# 10leds.net
KiCad netlist of a schematic drawn in EAGLE
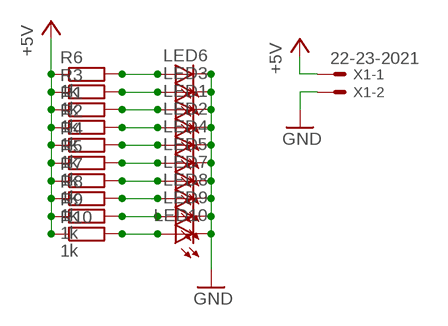
[diagram p0: schematic, sheet 1]

(export (version "E")
  (design (tool "Eeschema 10.0.6"))
  (components
    (comp (ref "LED1")
      (value "LED3MM")
      (footprint "eagle-import:LED3MM")
      (libsource (lib "eagle-import") (part "LED3MM"))
    )
    (comp (ref "LED2")
      (value "LED3MM")
      (footprint "eagle-import:LED3MM")
      (libsource (lib "eagle-import") (part "LED3MM"))
    )
    (comp (ref "LED3")
      (value "LED3MM")
      (footprint "eagle-import:LED3MM")
      (libsource (lib "eagle-import") (part "LED3MM"))
    )
    (comp (ref "LED4")
      (value "LED3MM")
      (footprint "eagle-import:LED3MM")
      (libsource (lib "eagle-import") (part "LED3MM"))
    )
    (comp (ref "LED5")
      (value "LED3MM")
      (footprint "eagle-import:LED3MM")
      (libsource (lib "eagle-import") (part "LED3MM"))
    )
    (comp (ref "LED6")
      (value "LED3MM")
      (footprint "eagle-import:LED3MM")
      (libsource (lib "eagle-import") (part "LED3MM"))
    )
    (comp (ref "LED7")
      (value "LED3MM")
      (footprint "eagle-import:LED3MM")
      (libsource (lib "eagle-import") (part "LED3MM"))
    )
    (comp (ref "LED8")
      (value "LED3MM")
      (footprint "eagle-import:LED3MM")
      (libsource (lib "eagle-import") (part "LED3MM"))
    )
    (comp (ref "LED9")
      (value "LED3MM")
      (footprint "eagle-import:LED3MM")
      (libsource (lib "eagle-import") (part "LED3MM"))
    )
    (comp (ref "LED10")
      (value "LED3MM")
      (footprint "eagle-import:LED3MM")
      (libsource (lib "eagle-import") (part "LED3MM"))
    )
    (comp (ref "R1")
      (value "1k")
      (footprint "eagle-import:M1206")
      (libsource (lib "eagle-import") (part "R-EU_M1206"))
    )
    (comp (ref "R2")
      (value "1k")
      (footprint "eagle-import:M1206")
      (libsource (lib "eagle-import") (part "R-EU_M1206"))
    )
    (comp (ref "R3")
      (value "1k")
      (footprint "eagle-import:M1206")
      (libsource (lib "eagle-import") (part "R-EU_M1206"))
    )
    (comp (ref "R4")
      (value "1k")
      (footprint "eagle-import:M1206")
      (libsource (lib "eagle-import") (part "R-EU_M1206"))
    )
    (comp (ref "R5")
      (value "1k")
      (footprint "eagle-import:M1206")
      (libsource (lib "eagle-import") (part "R-EU_M1206"))
    )
    (comp (ref "R6")
      (value "1k")
      (footprint "eagle-import:M1206")
      (libsource (lib "eagle-import") (part "R-EU_M1206"))
    )
    (comp (ref "R7")
      (value "1k")
      (footprint "eagle-import:M1206")
      (libsource (lib "eagle-import") (part "R-EU_M1206"))
    )
    (comp (ref "R8")
      (value "1k")
      (footprint "eagle-import:M1206")
      (libsource (lib "eagle-import") (part "R-EU_M1206"))
    )
    (comp (ref "R9")
      (value "1k")
      (footprint "eagle-import:M1206")
      (libsource (lib "eagle-import") (part "R-EU_M1206"))
    )
    (comp (ref "R10")
      (value "1k")
      (footprint "eagle-import:M1206")
      (libsource (lib "eagle-import") (part "R-EU_M1206"))
    )
    (comp (ref "X1")
      (value "22-23-2021")
      (footprint "eagle-import:22-23-2021")
      (fields (field (name "MF") "MOLEX"))
      (libsource (lib "eagle-import") (part "22-23-2021"))
    )
  )
  (nets
    (net (code "1") (name "+5V") (class "Default")
      (node (ref "R1") (pin "1") (pinfunction "1_1") (pintype "passive"))
      (node (ref "R10") (pin "1") (pinfunction "1_1") (pintype "passive"))
      (node (ref "R2") (pin "1") (pinfunction "1_1") (pintype "passive"))
      (node (ref "R3") (pin "1") (pinfunction "1_1") (pintype "passive"))
      (node (ref "R4") (pin "1") (pinfunction "1_1") (pintype "passive"))
      (node (ref "R5") (pin "1") (pinfunction "1_1") (pintype "passive"))
      (node (ref "R6") (pin "1") (pinfunction "1_1") (pintype "passive"))
      (node (ref "R7") (pin "1") (pinfunction "1_1") (pintype "passive"))
      (node (ref "R8") (pin "1") (pinfunction "1_1") (pintype "passive"))
      (node (ref "R9") (pin "1") (pinfunction "1_1") (pintype "passive"))
      (node (ref "X1") (pin "1") (pinfunction "S_1") (pintype "passive"))
    )
    (net (code "2") (name "GND") (class "Default")
      (node (ref "LED1") (pin "K") (pinfunction "C_K") (pintype "passive"))
      (node (ref "LED10") (pin "K") (pinfunction "C_K") (pintype "passive"))
      (node (ref "LED2") (pin "K") (pinfunction "C_K") (pintype "passive"))
      (node (ref "LED3") (pin "K") (pinfunction "C_K") (pintype "passive"))
      (node (ref "LED4") (pin "K") (pinfunction "C_K") (pintype "passive"))
      (node (ref "LED5") (pin "K") (pinfunction "C_K") (pintype "passive"))
      (node (ref "LED6") (pin "K") (pinfunction "C_K") (pintype "passive"))
      (node (ref "LED7") (pin "K") (pinfunction "C_K") (pintype "passive"))
      (node (ref "LED8") (pin "K") (pinfunction "C_K") (pintype "passive"))
      (node (ref "LED9") (pin "K") (pinfunction "C_K") (pintype "passive"))
      (node (ref "X1") (pin "2") (pinfunction "S_2") (pintype "passive"))
    )
    (net (code "3") (name "Net-(LED1-PadA)") (class "Default")
      (node (ref "LED1") (pin "A") (pinfunction "A_A") (pintype "passive"))
      (node (ref "R1") (pin "2") (pinfunction "2_2") (pintype "passive"))
    )
    (net (code "4") (name "Net-(LED2-PadA)") (class "Default")
      (node (ref "LED2") (pin "A") (pinfunction "A_A") (pintype "passive"))
      (node (ref "R2") (pin "2") (pinfunction "2_2") (pintype "passive"))
    )
    (net (code "5") (name "Net-(LED3-PadA)") (class "Default")
      (node (ref "LED3") (pin "A") (pinfunction "A_A") (pintype "passive"))
      (node (ref "R3") (pin "2") (pinfunction "2_2") (pintype "passive"))
    )
    (net (code "6") (name "Net-(LED4-PadA)") (class "Default")
      (node (ref "LED4") (pin "A") (pinfunction "A_A") (pintype "passive"))
      (node (ref "R4") (pin "2") (pinfunction "2_2") (pintype "passive"))
    )
    (net (code "7") (name "Net-(LED5-PadA)") (class "Default")
      (node (ref "LED5") (pin "A") (pinfunction "A_A") (pintype "passive"))
      (node (ref "R5") (pin "2") (pinfunction "2_2") (pintype "passive"))
    )
    (net (code "8") (name "Net-(LED6-PadA)") (class "Default")
      (node (ref "LED6") (pin "A") (pinfunction "A_A") (pintype "passive"))
      (node (ref "R6") (pin "2") (pinfunction "2_2") (pintype "passive"))
    )
    (net (code "9") (name "Net-(LED7-PadA)") (class "Default")
      (node (ref "LED7") (pin "A") (pinfunction "A_A") (pintype "passive"))
      (node (ref "R7") (pin "2") (pinfunction "2_2") (pintype "passive"))
    )
    (net (code "10") (name "Net-(LED8-PadA)") (class "Default")
      (node (ref "LED8") (pin "A") (pinfunction "A_A") (pintype "passive"))
      (node (ref "R8") (pin "2") (pinfunction "2_2") (pintype "passive"))
    )
    (net (code "11") (name "Net-(LED9-PadA)") (class "Default")
      (node (ref "LED9") (pin "A") (pinfunction "A_A") (pintype "passive"))
      (node (ref "R9") (pin "2") (pinfunction "2_2") (pintype "passive"))
    )
    (net (code "12") (name "Net-(LED10-PadA)") (class "Default")
      (node (ref "LED10") (pin "A") (pinfunction "A_A") (pintype "passive"))
      (node (ref "R10") (pin "2") (pinfunction "2_2") (pintype "passive"))
    )
  )
)
